# ernest.net
KiCad netlist of a schematic drawn in EAGLE
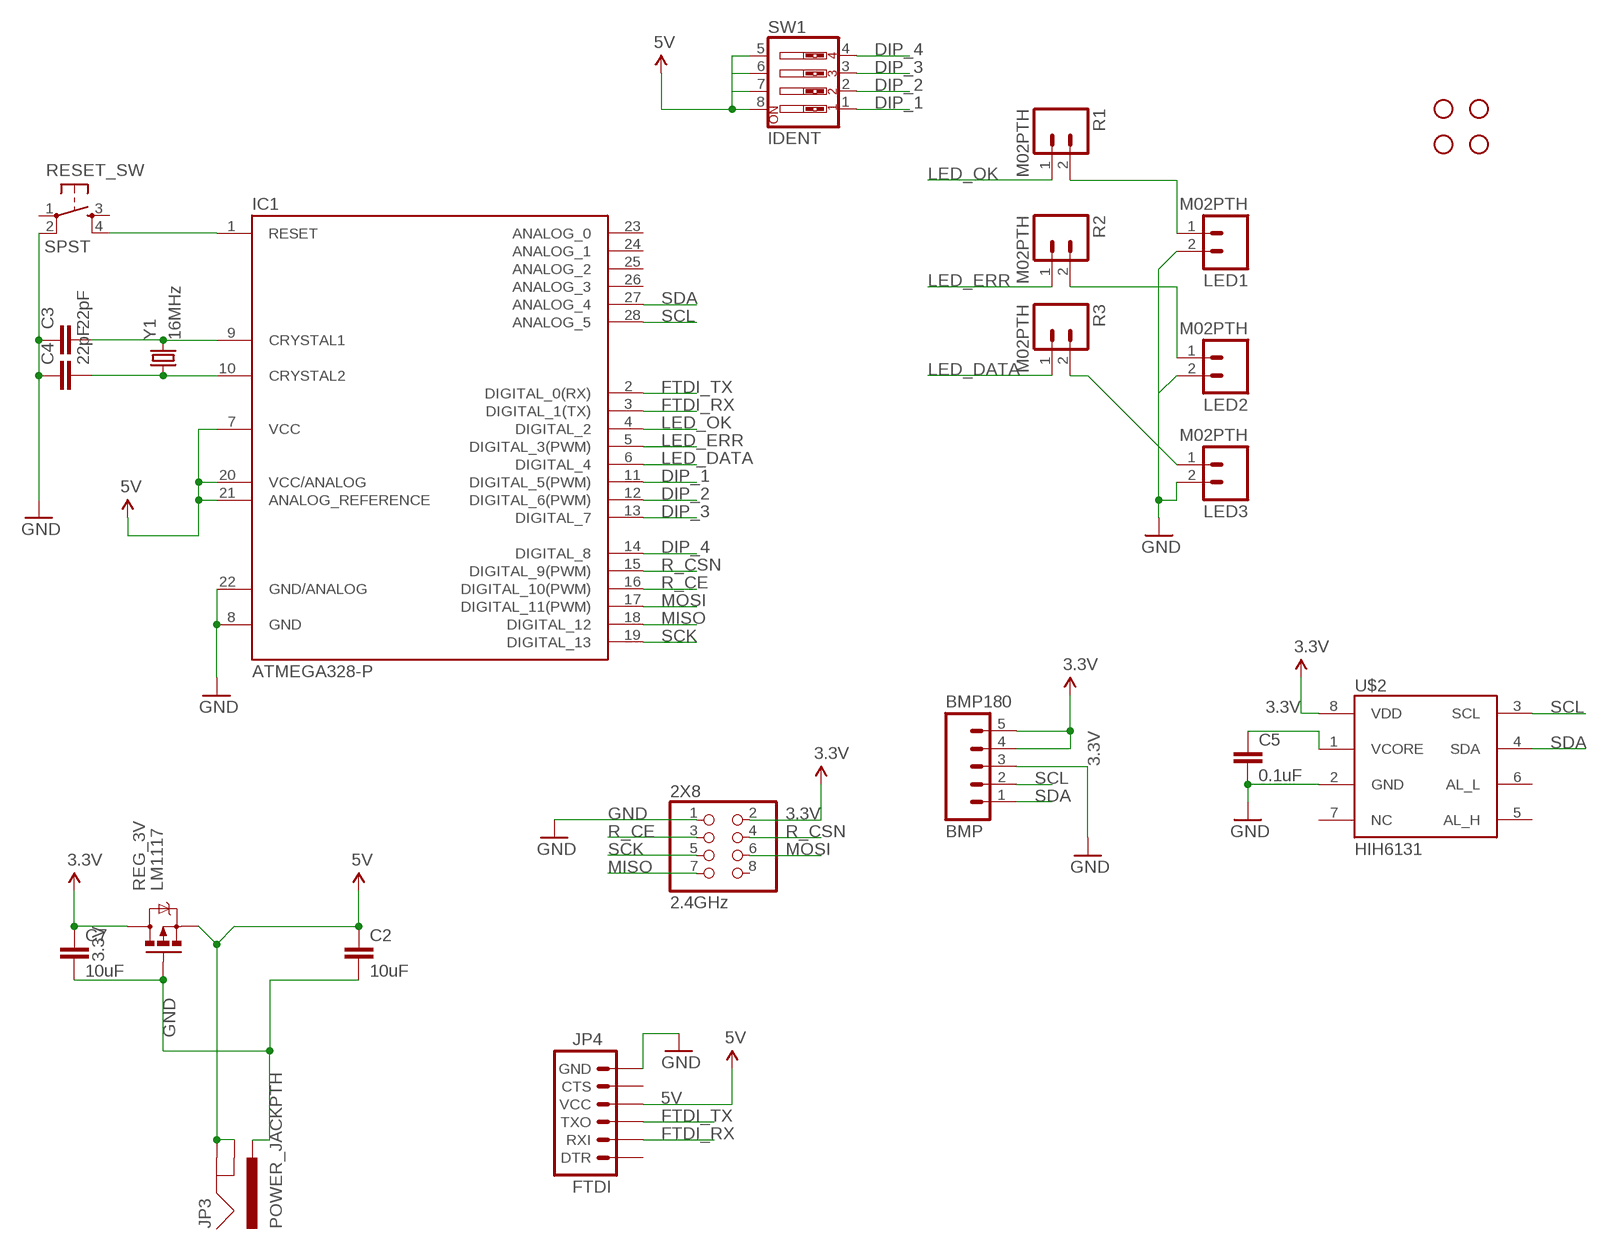
[diagram p0: schematic, sheet 1]

(export (version "E")
  (design (tool "Eeschema 10.0.6"))
  (components
    (comp (ref "2X8")
      (value "2.4GHz")
      (footprint "eagle-import:2X04")
      (libsource (lib "eagle-import") (part "PINHD-2X4"))
    )
    (comp (ref "BMP180")
      (value "BMP")
      (footprint "eagle-import:1X05")
      (libsource (lib "eagle-import") (part "M05PTH"))
    )
    (comp (ref "C2")
      (value "10uF")
      (footprint "eagle-import:CAP-PTH-SMALL")
      (libsource (lib "eagle-import") (part "CAPPTH"))
    )
    (comp (ref "C3")
      (value "22pF")
      (footprint "eagle-import:CAP-PTH-SMALL")
      (libsource (lib "eagle-import") (part "CAPPTH"))
    )
    (comp (ref "C4")
      (value "22pF")
      (footprint "eagle-import:CAP-PTH-SMALL")
      (libsource (lib "eagle-import") (part "CAPPTH"))
    )
    (comp (ref "C5")
      (value "0.1uF")
      (footprint "eagle-import:CAP-PTH-SMALL")
      (libsource (lib "eagle-import") (part "CAPPTH"))
    )
    (comp (ref "C7")
      (value "10uF")
      (footprint "eagle-import:CAP-PTH-SMALL")
      (libsource (lib "eagle-import") (part "CAPPTH"))
    )
    (comp (ref "IC1")
      (value "ATMEGA328-P")
      (footprint "eagle-import:DIL28-3")
      (libsource (lib "eagle-import") (part "ATMEGA168-PU"))
    )
    (comp (ref "JP3")
      (value "POWER_JACKPTH")
      (footprint "eagle-import:POWER_JACK_PTH")
      (libsource (lib "eagle-import") (part "POWER_JACKPTH"))
    )
    (comp (ref "JP4")
      (value "FTDI")
      (footprint "eagle-import:1X06")
      (libsource (lib "eagle-import") (part "ARDUINO_SERIAL_PROGRAMPTH"))
    )
    (comp (ref "LED1")
      (value "M02PTH")
      (footprint "eagle-import:1X02")
      (libsource (lib "eagle-import") (part "M02PTH"))
    )
    (comp (ref "LED2")
      (value "M02PTH")
      (footprint "eagle-import:1X02")
      (libsource (lib "eagle-import") (part "M02PTH"))
    )
    (comp (ref "LED3")
      (value "M02PTH")
      (footprint "eagle-import:1X02")
      (libsource (lib "eagle-import") (part "M02PTH"))
    )
    (comp (ref "R1")
      (value "M02PTH")
      (footprint "eagle-import:1X02")
      (libsource (lib "eagle-import") (part "M02PTH"))
    )
    (comp (ref "R2")
      (value "M02PTH")
      (footprint "eagle-import:1X02")
      (libsource (lib "eagle-import") (part "M02PTH"))
    )
    (comp (ref "R3")
      (value "M02PTH")
      (footprint "eagle-import:1X02")
      (libsource (lib "eagle-import") (part "M02PTH"))
    )
    (comp (ref "REG_3V")
      (value "LM1117")
      (footprint "eagle-import:TO220V")
      (libsource (lib "eagle-import") (part "MOSFET-PCHANNELFQP27P06"))
    )
    (comp (ref "RESET_SW")
      (value "SPST")
      (footprint "eagle-import:TAC-SWITCH-PTH")
      (libsource (lib "eagle-import") (part "TACTILE-SWITCH-PTH"))
    )
    (comp (ref "STANDOFF1")
      (value "STAND-OFF")
      (footprint "eagle-import:STAND-OFF")
      (libsource (lib "eagle-import") (part "STAND-OFF"))
    )
    (comp (ref "STANDOFF2")
      (value "STAND-OFF")
      (footprint "eagle-import:STAND-OFF")
      (libsource (lib "eagle-import") (part "STAND-OFF"))
    )
    (comp (ref "STANDOFF3")
      (value "STAND-OFF")
      (footprint "eagle-import:STAND-OFF")
      (libsource (lib "eagle-import") (part "STAND-OFF"))
    )
    (comp (ref "STANDOFF4")
      (value "STAND-OFF")
      (footprint "eagle-import:STAND-OFF")
      (libsource (lib "eagle-import") (part "STAND-OFF"))
    )
    (comp (ref "SW1")
      (value "IDENT")
      (footprint "eagle-import:EDG-04")
      (libsource (lib "eagle-import") (part "SW_DIP-4"))
    )
    (comp (ref "U$2")
      (value "HIH6131")
      (footprint "eagle-import:SOIC8")
      (libsource (lib "eagle-import") (part "HIH6131"))
    )
    (comp (ref "Y1")
      (value "16MHz")
      (footprint "eagle-import:HC49US")
      (libsource (lib "eagle-import") (part "CRYSTALHC49US"))
    )
  )
  (nets
    (net (code "1") (name "/DIP_1") (class "Default")
      (node (ref "IC1") (pin "11") (pinfunction "DIGITAL_5(PWM)_11") (pintype "bidirectional"))
      (node (ref "SW1") (pin "1") (pinfunction "1_1") (pintype "passive"))
    )
    (net (code "2") (name "/DIP_2") (class "Default")
      (node (ref "IC1") (pin "12") (pinfunction "DIGITAL_6(PWM)_12") (pintype "bidirectional"))
      (node (ref "SW1") (pin "2") (pinfunction "2_2") (pintype "passive"))
    )
    (net (code "3") (name "/DIP_3") (class "Default")
      (node (ref "IC1") (pin "13") (pinfunction "DIGITAL_7_13") (pintype "bidirectional"))
      (node (ref "SW1") (pin "3") (pinfunction "3_3") (pintype "passive"))
    )
    (net (code "4") (name "/DIP_4") (class "Default")
      (node (ref "IC1") (pin "14") (pinfunction "DIGITAL_8_14") (pintype "bidirectional"))
      (node (ref "SW1") (pin "4") (pinfunction "4_4") (pintype "passive"))
    )
    (net (code "5") (name "/FTDI_RX") (class "Default")
      (node (ref "IC1") (pin "3") (pinfunction "DIGITAL_1(TX)_3") (pintype "bidirectional"))
      (node (ref "JP4") (pin "2") (pinfunction "RXI_2") (pintype "passive"))
    )
    (net (code "6") (name "/FTDI_TX") (class "Default")
      (node (ref "IC1") (pin "2") (pinfunction "DIGITAL_0(RX)_2") (pintype "bidirectional"))
      (node (ref "JP4") (pin "3") (pinfunction "TXO_3") (pintype "passive"))
    )
    (net (code "7") (name "/LED_DATA") (class "Default")
      (node (ref "IC1") (pin "6") (pinfunction "DIGITAL_4_6") (pintype "bidirectional"))
      (node (ref "R3") (pin "1") (pinfunction "1_1") (pintype "passive"))
    )
    (net (code "8") (name "/LED_ERR") (class "Default")
      (node (ref "IC1") (pin "5") (pinfunction "DIGITAL_3(PWM)_5") (pintype "bidirectional"))
      (node (ref "R2") (pin "1") (pinfunction "1_1") (pintype "passive"))
    )
    (net (code "9") (name "/LED_OK") (class "Default")
      (node (ref "IC1") (pin "4") (pinfunction "DIGITAL_2_4") (pintype "bidirectional"))
      (node (ref "R1") (pin "1") (pinfunction "1_1") (pintype "passive"))
    )
    (net (code "10") (name "/MISO") (class "Default")
      (node (ref "2X8") (pin "7") (pinfunction "7_7") (pintype "passive"))
      (node (ref "IC1") (pin "18") (pinfunction "DIGITAL_12_18") (pintype "bidirectional"))
    )
    (net (code "11") (name "/MOSI") (class "Default")
      (node (ref "2X8") (pin "6") (pinfunction "6_6") (pintype "passive"))
      (node (ref "IC1") (pin "17") (pinfunction "DIGITAL_11(PWM)_17") (pintype "bidirectional"))
    )
    (net (code "12") (name "/R_CE") (class "Default")
      (node (ref "2X8") (pin "3") (pinfunction "3_3") (pintype "passive"))
      (node (ref "IC1") (pin "16") (pinfunction "DIGITAL_10(PWM)_16") (pintype "bidirectional"))
    )
    (net (code "13") (name "/R_CSN") (class "Default")
      (node (ref "2X8") (pin "4") (pinfunction "4_4") (pintype "passive"))
      (node (ref "IC1") (pin "15") (pinfunction "DIGITAL_9(PWM)_15") (pintype "bidirectional"))
    )
    (net (code "14") (name "/SCK") (class "Default")
      (node (ref "2X8") (pin "5") (pinfunction "5_5") (pintype "passive"))
      (node (ref "IC1") (pin "19") (pinfunction "DIGITAL_13_19") (pintype "bidirectional"))
    )
    (net (code "15") (name "/SCL") (class "Default")
      (node (ref "BMP180") (pin "2") (pinfunction "2_2") (pintype "passive"))
      (node (ref "IC1") (pin "28") (pinfunction "ANALOG_5_28") (pintype "bidirectional"))
      (node (ref "U$2") (pin "3") (pinfunction "SCL_3") (pintype "bidirectional"))
    )
    (net (code "16") (name "/SDA") (class "Default")
      (node (ref "BMP180") (pin "1") (pinfunction "1_1") (pintype "passive"))
      (node (ref "IC1") (pin "27") (pinfunction "ANALOG_4_27") (pintype "bidirectional"))
      (node (ref "U$2") (pin "4") (pinfunction "SDA_4") (pintype "bidirectional"))
    )
    (net (code "17") (name "3.3V") (class "Default")
      (node (ref "2X8") (pin "2") (pinfunction "2_2") (pintype "passive"))
      (node (ref "BMP180") (pin "4") (pinfunction "4_4") (pintype "passive"))
      (node (ref "BMP180") (pin "5") (pinfunction "5_5") (pintype "passive"))
      (node (ref "C7") (pin "1") (pinfunction "1_1") (pintype "passive"))
      (node (ref "REG_3V") (pin "2") (pinfunction "D_2") (pintype "passive"))
      (node (ref "U$2") (pin "8") (pinfunction "VDD_8") (pintype "bidirectional"))
    )
    (net (code "18") (name "5V") (class "Default")
      (node (ref "C2") (pin "1") (pinfunction "1_1") (pintype "passive"))
      (node (ref "IC1") (pin "20") (pinfunction "VCC/ANALOG_20") (pintype "passive"))
      (node (ref "IC1") (pin "21") (pinfunction "ANALOG_REFERENCE_21") (pintype "passive"))
      (node (ref "IC1") (pin "7") (pinfunction "VCC_7") (pintype "power_in"))
      (node (ref "JP3") (pin "GND") (pinfunction "GND_GND") (pintype "bidirectional"))
      (node (ref "JP3") (pin "GNDBREAK") (pinfunction "GNDBREAK_GNDBREAK") (pintype "bidirectional"))
      (node (ref "JP4") (pin "4") (pinfunction "VCC_4") (pintype "passive"))
      (node (ref "REG_3V") (pin "3") (pinfunction "S_3") (pintype "passive"))
      (node (ref "SW1") (pin "5") (pinfunction "5_5") (pintype "passive"))
      (node (ref "SW1") (pin "6") (pinfunction "6_6") (pintype "passive"))
      (node (ref "SW1") (pin "7") (pinfunction "7_7") (pintype "passive"))
      (node (ref "SW1") (pin "8") (pinfunction "8_8") (pintype "passive"))
    )
    (net (code "19") (name "GND") (class "Default")
      (node (ref "2X8") (pin "1") (pinfunction "1_1") (pintype "passive"))
      (node (ref "BMP180") (pin "3") (pinfunction "3_3") (pintype "passive"))
      (node (ref "C2") (pin "2") (pinfunction "2_2") (pintype "passive"))
      (node (ref "C3") (pin "1") (pinfunction "1_1") (pintype "passive"))
      (node (ref "C4") (pin "1") (pinfunction "1_1") (pintype "passive"))
      (node (ref "C5") (pin "2") (pinfunction "2_2") (pintype "passive"))
      (node (ref "C7") (pin "2") (pinfunction "2_2") (pintype "passive"))
      (node (ref "IC1") (pin "22") (pinfunction "GND/ANALOG_22") (pintype "power_in"))
      (node (ref "IC1") (pin "8") (pinfunction "GND_8") (pintype "power_in"))
      (node (ref "JP3") (pin "PWR") (pinfunction "PWR_PWR") (pintype "bidirectional"))
      (node (ref "JP4") (pin "6") (pinfunction "GND_6") (pintype "passive"))
      (node (ref "LED1") (pin "2") (pinfunction "2_2") (pintype "passive"))
      (node (ref "LED2") (pin "2") (pinfunction "2_2") (pintype "passive"))
      (node (ref "LED3") (pin "2") (pinfunction "2_2") (pintype "passive"))
      (node (ref "REG_3V") (pin "1") (pinfunction "G_1") (pintype "passive"))
      (node (ref "RESET_SW") (pin "2") (pinfunction "2_2") (pintype "passive"))
      (node (ref "U$2") (pin "2") (pinfunction "GND_2") (pintype "bidirectional"))
    )
    (net (code "20") (name "Net-(IC1-CRYSTAL1)") (class "Default")
      (node (ref "C3") (pin "2") (pinfunction "2_2") (pintype "passive"))
      (node (ref "IC1") (pin "9") (pinfunction "CRYSTAL1_9") (pintype "bidirectional"))
      (node (ref "Y1") (pin "2") (pinfunction "2_2") (pintype "passive"))
    )
    (net (code "21") (name "Net-(IC1-CRYSTAL2)") (class "Default")
      (node (ref "C4") (pin "2") (pinfunction "2_2") (pintype "passive"))
      (node (ref "IC1") (pin "10") (pinfunction "CRYSTAL2_10") (pintype "bidirectional"))
      (node (ref "Y1") (pin "1") (pinfunction "1_1") (pintype "passive"))
    )
    (net (code "22") (name "Net-(IC1-RESET)") (class "Default")
      (node (ref "IC1") (pin "1") (pinfunction "RESET_1") (pintype "bidirectional"))
      (node (ref "RESET_SW") (pin "4") (pinfunction "4_4") (pintype "passive"))
    )
    (net (code "23") (name "Net-(LED1-Pad1)") (class "Default")
      (node (ref "LED1") (pin "1") (pinfunction "1_1") (pintype "passive"))
      (node (ref "R1") (pin "2") (pinfunction "2_2") (pintype "passive"))
    )
    (net (code "24") (name "Net-(LED2-Pad1)") (class "Default")
      (node (ref "LED2") (pin "1") (pinfunction "1_1") (pintype "passive"))
      (node (ref "R2") (pin "2") (pinfunction "2_2") (pintype "passive"))
    )
    (net (code "25") (name "Net-(LED3-Pad1)") (class "Default")
      (node (ref "LED3") (pin "1") (pinfunction "1_1") (pintype "passive"))
      (node (ref "R3") (pin "2") (pinfunction "2_2") (pintype "passive"))
    )
    (net (code "26") (name "Net-(U$2-VCORE)") (class "Default")
      (node (ref "C5") (pin "1") (pinfunction "1_1") (pintype "passive"))
      (node (ref "U$2") (pin "1") (pinfunction "VCORE_1") (pintype "bidirectional"))
    )
    (net (code "27") (name "unconnected-(2X8-Pad8)") (class "Default")
      (node (ref "2X8") (pin "8") (pinfunction "8_8") (pintype "passive"))
    )
    (net (code "28") (name "unconnected-(IC1-ANALOG_0-Pad23)") (class "Default")
      (node (ref "IC1") (pin "23") (pinfunction "ANALOG_0_23") (pintype "bidirectional"))
    )
    (net (code "29") (name "unconnected-(IC1-ANALOG_1-Pad24)") (class "Default")
      (node (ref "IC1") (pin "24") (pinfunction "ANALOG_1_24") (pintype "bidirectional"))
    )
    (net (code "30") (name "unconnected-(IC1-ANALOG_2-Pad25)") (class "Default")
      (node (ref "IC1") (pin "25") (pinfunction "ANALOG_2_25") (pintype "bidirectional"))
    )
    (net (code "31") (name "unconnected-(IC1-ANALOG_3-Pad26)") (class "Default")
      (node (ref "IC1") (pin "26") (pinfunction "ANALOG_3_26") (pintype "bidirectional"))
    )
    (net (code "32") (name "unconnected-(JP4-CTS-Pad5)") (class "Default")
      (node (ref "JP4") (pin "5") (pinfunction "CTS_5") (pintype "passive"))
    )
    (net (code "33") (name "unconnected-(JP4-DTR-Pad1)") (class "Default")
      (node (ref "JP4") (pin "1") (pinfunction "DTR_1") (pintype "passive"))
    )
    (net (code "34") (name "unconnected-(RESET_SW-Pad1)") (class "Default")
      (node (ref "RESET_SW") (pin "1") (pinfunction "1_1") (pintype "passive"))
    )
    (net (code "35") (name "unconnected-(RESET_SW-Pad3)") (class "Default")
      (node (ref "RESET_SW") (pin "3") (pinfunction "3_3") (pintype "passive"))
    )
    (net (code "36") (name "unconnected-(U$2-AL_H-Pad5)") (class "Default")
      (node (ref "U$2") (pin "5") (pinfunction "AL_H_5") (pintype "bidirectional"))
    )
    (net (code "37") (name "unconnected-(U$2-AL_L-Pad6)") (class "Default")
      (node (ref "U$2") (pin "6") (pinfunction "AL_L_6") (pintype "bidirectional"))
    )
    (net (code "38") (name "unconnected-(U$2-NC-Pad7)") (class "Default")
      (node (ref "U$2") (pin "7") (pinfunction "NC_7") (pintype "bidirectional"))
    )
  )
)
